# switchy-stamp-buckeroo-mk-1.net
KiCad netlist of a schematic drawn in EAGLE
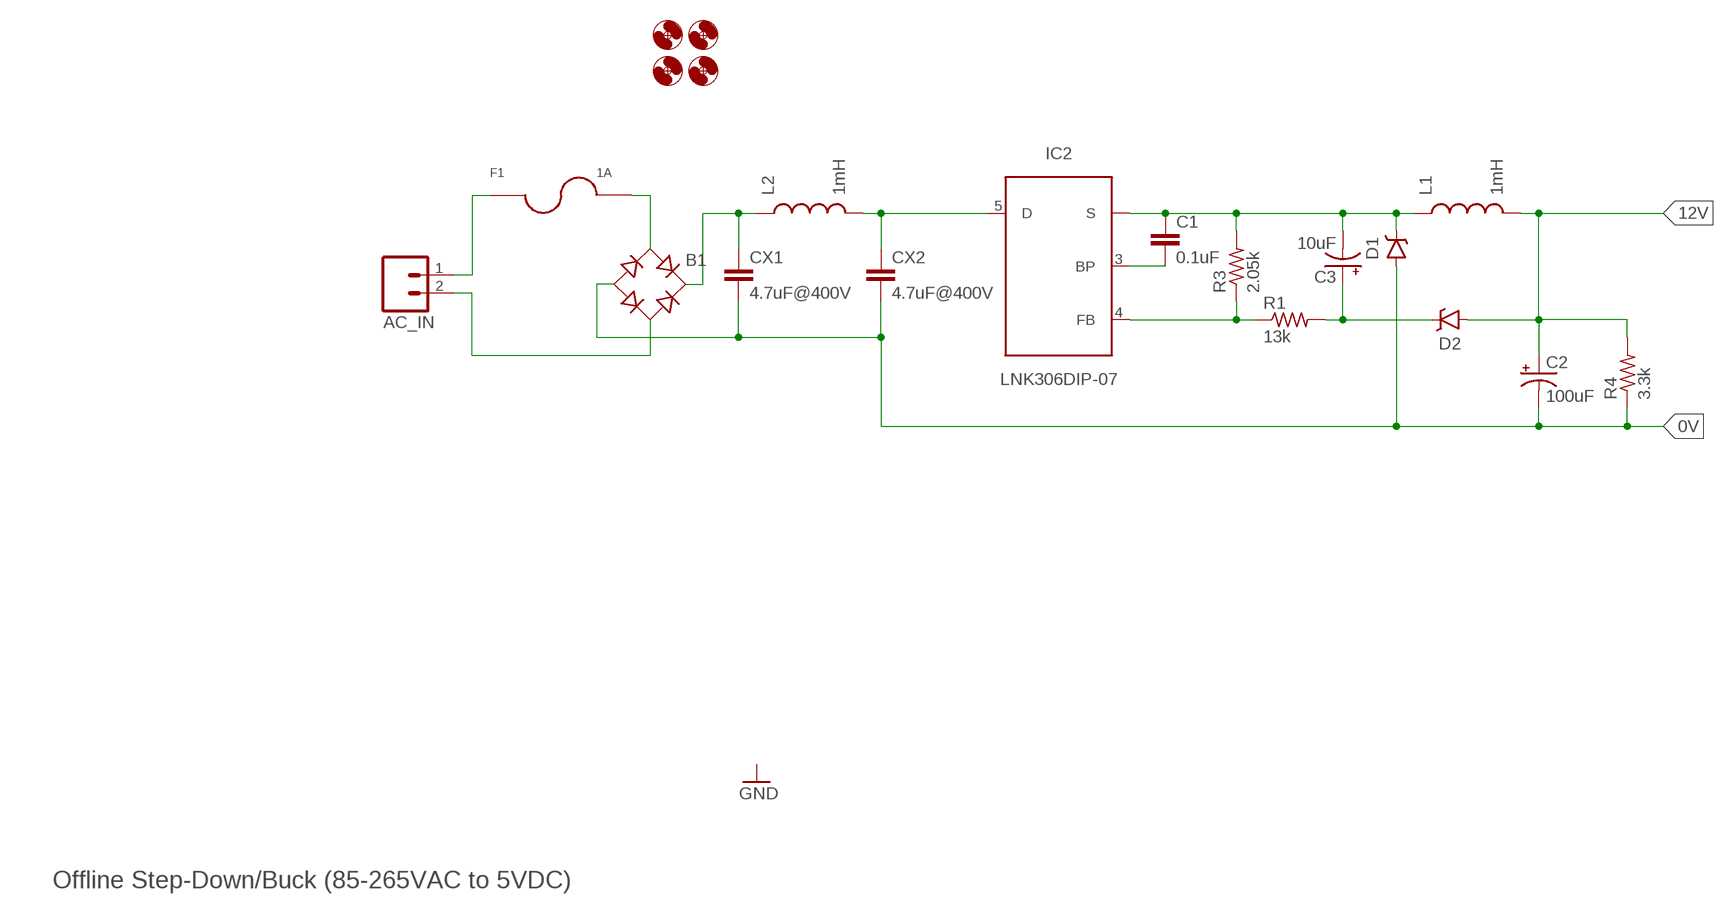
[diagram p0: schematic, sheet 1]

(export (version "E")
  (design (tool "Eeschema 10.0.6"))
  (components
    (comp (ref "AC_IN")
      (value "M023.5MM")
      (footprint "eagle-import:SCREWTERMINAL-3.5MM-2")
      (libsource (lib "eagle-import") (part "M023.5MM"))
    )
    (comp (ref "B1")
      (value "RB1ANOSUCK")
      (footprint "eagle-import:RB1A-NOSUCK")
      (libsource (lib "eagle-import") (part "RB1ANOSUCK"))
    )
    (comp (ref "C1")
      (value "0.1uF")
      (footprint "eagle-import:C025-024X044")
      (libsource (lib "eagle-import") (part "CAPACITOR-CERAMIC025-024X044"))
    )
    (comp (ref "C2")
      (value "100uF")
      (footprint "eagle-import:E3,5-8")
      (libsource (lib "eagle-import") (part "CAPACITOR-POLARIZEDE3.5-8"))
    )
    (comp (ref "C3")
      (value "10uF")
      (footprint "eagle-import:E3,5-8")
      (libsource (lib "eagle-import") (part "CAPACITOR-POLARIZEDE3.5-8"))
    )
    (comp (ref "CX1")
      (value "4.7uF@400V")
      (footprint "eagle-import:XC10B5")
      (libsource (lib "eagle-import") (part "CXXC10B5"))
    )
    (comp (ref "CX2")
      (value "4.7uF@400V")
      (footprint "eagle-import:XC10B5")
      (libsource (lib "eagle-import") (part "CXXC10B5"))
    )
    (comp (ref "D1")
      (value "1N5819")
      (footprint "eagle-import:DIODE-10.16MM")
      (libsource (lib "eagle-import") (part "DIODE-SCHOTTKYPTH-10.16MM"))
    )
    (comp (ref "D2")
      (value "1N5819")
      (footprint "eagle-import:DIODE-10.16MM")
      (libsource (lib "eagle-import") (part "DIODE-SCHOTTKYPTH-10.16MM"))
    )
    (comp (ref "F1")
      (value "1A")
      (footprint "eagle-import:FUSE-2AG")
      (libsource (lib "eagle-import") (part "FUSE5X20MM-2"))
    )
    (comp (ref "H1")
      (value "HOLE#2")
      (footprint "eagle-import:HOLE-#2")
      (libsource (lib "eagle-import") (part "HOLE#2"))
    )
    (comp (ref "H2")
      (value "HOLE#2")
      (footprint "eagle-import:HOLE-#2")
      (libsource (lib "eagle-import") (part "HOLE#2"))
    )
    (comp (ref "H3")
      (value "HOLE#2")
      (footprint "eagle-import:HOLE-#2")
      (libsource (lib "eagle-import") (part "HOLE#2"))
    )
    (comp (ref "H4")
      (value "HOLE#2")
      (footprint "eagle-import:HOLE-#2")
      (libsource (lib "eagle-import") (part "HOLE#2"))
    )
    (comp (ref "IC2")
      (value "LNK306DIP-07")
      (footprint "eagle-import:DIP-07")
      (libsource (lib "eagle-import") (part "LNK306DIP-07"))
    )
    (comp (ref "L1")
      (value "1mH")
      (footprint "eagle-import:INDUCTOR-AXIAL-PTH-10.16MM")
      (libsource (lib "eagle-import") (part "INDUCTORAXIAL-PTH-10.16MM"))
    )
    (comp (ref "L2")
      (value "1mH")
      (footprint "eagle-import:INDUCTOR-AXIAL-PTH-10.16MM")
      (libsource (lib "eagle-import") (part "INDUCTORAXIAL-PTH-10.16MM"))
    )
    (comp (ref "R1")
      (value "13k")
      (footprint "eagle-import:RESISTOR-AXIAL-PTH-6.35MM")
      (libsource (lib "eagle-import") (part "RESISTORPTH-AXIAL-6.35MM"))
    )
    (comp (ref "R3")
      (value "2.05k")
      (footprint "eagle-import:RESISTOR-AXIAL-PTH-6.35MM")
      (libsource (lib "eagle-import") (part "RESISTORPTH-AXIAL-6.35MM"))
    )
    (comp (ref "R4")
      (value "3.3k")
      (footprint "eagle-import:RESISTOR-AXIAL-PTH-6.35MM")
      (libsource (lib "eagle-import") (part "RESISTORPTH-AXIAL-6.35MM"))
    )
  )
  (nets
    (net (code "1") (name "0V") (class "Default")
      (node (ref "B1") (pin "-") (pinfunction "-_-") (pintype "passive"))
      (node (ref "C2") (pin "-") (pinfunction "-_-") (pintype "passive"))
      (node (ref "CX1") (pin "2") (pinfunction "2_2") (pintype "passive"))
      (node (ref "CX2") (pin "2") (pinfunction "2_2") (pintype "passive"))
      (node (ref "D1") (pin "A") (pinfunction "A_A") (pintype "passive"))
      (node (ref "R4") (pin "P$1") (pinfunction "1_P$1") (pintype "passive"))
    )
    (net (code "2") (name "12V") (class "Default")
      (node (ref "C2") (pin "+") (pinfunction "+_+") (pintype "passive"))
      (node (ref "D2") (pin "A") (pinfunction "A_A") (pintype "passive"))
      (node (ref "L1") (pin "P$2") (pinfunction "2_P$2") (pintype "passive"))
      (node (ref "R4") (pin "P$2") (pinfunction "2_P$2") (pintype "passive"))
    )
    (net (code "4") (name "Net-(AC_IN-Pad1)") (class "Default")
      (node (ref "AC_IN") (pin "1") (pinfunction "1_1") (pintype "passive"))
      (node (ref "F1") (pin "1") (pinfunction "1_1") (pintype "bidirectional"))
      (node (ref "F1") (pin "1@1") (pinfunction "1_1@1") (pintype "bidirectional"))
    )
    (net (code "5") (name "Net-(AC_IN-Pad2)") (class "Default")
      (node (ref "AC_IN") (pin "2") (pinfunction "2_2") (pintype "passive"))
      (node (ref "B1") (pin "AC2") (pinfunction "AC2_AC2") (pintype "passive"))
    )
    (net (code "6") (name "Net-(B1-PadAC1)") (class "Default")
      (node (ref "B1") (pin "AC1") (pinfunction "AC1_AC1") (pintype "passive"))
      (node (ref "F1") (pin "2") (pinfunction "2_2") (pintype "bidirectional"))
      (node (ref "F1") (pin "2@2") (pinfunction "2_2@2") (pintype "bidirectional"))
    )
    (net (code "7") (name "Net-(IC2-BP)") (class "Default")
      (node (ref "C1") (pin "2") (pinfunction "2_2") (pintype "passive"))
      (node (ref "IC2") (pin "3") (pinfunction "BP_3") (pintype "bidirectional"))
    )
    (net (code "8") (name "Net-(IC2-D)") (class "Default")
      (node (ref "CX2") (pin "1") (pinfunction "1_1") (pintype "passive"))
      (node (ref "IC2") (pin "5") (pinfunction "D_5") (pintype "bidirectional"))
      (node (ref "L2") (pin "P$2") (pinfunction "2_P$2") (pintype "passive"))
    )
    (net (code "9") (name "Net-(IC2-FB)") (class "Default")
      (node (ref "IC2") (pin "4") (pinfunction "FB_4") (pintype "bidirectional"))
      (node (ref "R1") (pin "P$1") (pinfunction "1_P$1") (pintype "passive"))
      (node (ref "R3") (pin "P$1") (pinfunction "1_P$1") (pintype "passive"))
    )
    (net (code "10") (name "Net-(L1-1)") (class "Default")
      (node (ref "C1") (pin "1") (pinfunction "1_1") (pintype "passive"))
      (node (ref "C3") (pin "-") (pinfunction "-_-") (pintype "passive"))
      (node (ref "D1") (pin "C") (pinfunction "C_C") (pintype "passive"))
      (node (ref "IC2") (pin "1") (pinfunction "S_1") (pintype "bidirectional"))
      (node (ref "IC2") (pin "2") (pinfunction "S_2") (pintype "bidirectional"))
      (node (ref "IC2") (pin "7") (pinfunction "S_7") (pintype "bidirectional"))
      (node (ref "IC2") (pin "8") (pinfunction "S_8") (pintype "bidirectional"))
      (node (ref "L1") (pin "P$1") (pinfunction "1_P$1") (pintype "passive"))
      (node (ref "R3") (pin "P$2") (pinfunction "2_P$2") (pintype "passive"))
    )
    (net (code "11") (name "Net-(L2-1)") (class "Default")
      (node (ref "B1") (pin "+") (pinfunction "+_+") (pintype "passive"))
      (node (ref "CX1") (pin "1") (pinfunction "1_1") (pintype "passive"))
      (node (ref "L2") (pin "P$1") (pinfunction "1_P$1") (pintype "passive"))
    )
    (net (code "12") (name "Net-(R1-2)") (class "Default")
      (node (ref "C3") (pin "+") (pinfunction "+_+") (pintype "passive"))
      (node (ref "D2") (pin "C") (pinfunction "C_C") (pintype "passive"))
      (node (ref "R1") (pin "P$2") (pinfunction "2_P$2") (pintype "passive"))
    )
  )
)
